# BMP180_breakout_v02.net
KiCad netlist of a schematic drawn in EAGLE
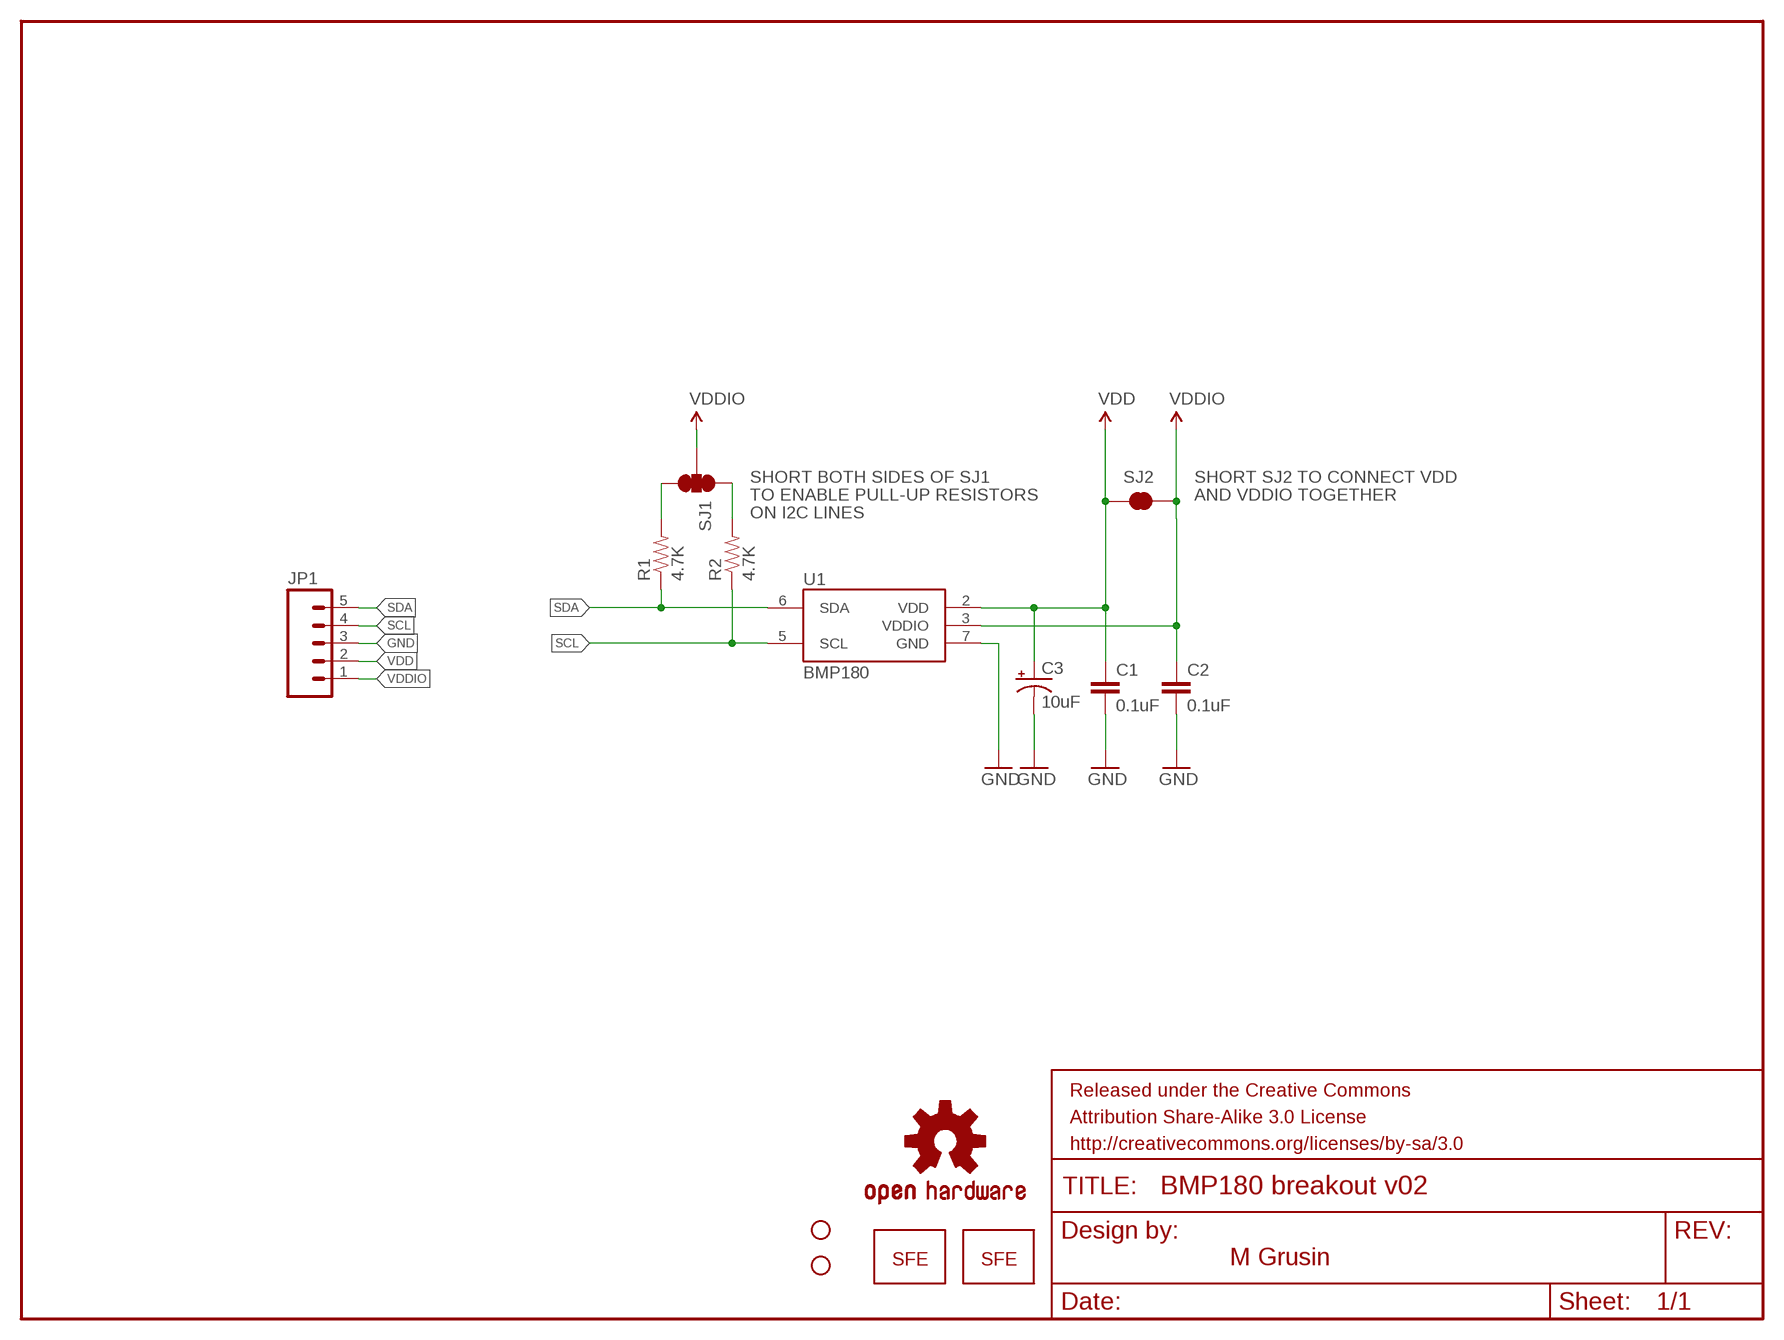
[diagram p0: schematic, sheet 1]

(export (version "E")
  (design (tool "Eeschema 10.0.6"))
  (components
    (comp (ref "C1")
      (value "0.1uF")
      (footprint "eagle-import:0603-CAP")
      (libsource (lib "eagle-import") (part "CAP0603-CAP"))
    )
    (comp (ref "C2")
      (value "0.1uF")
      (footprint "eagle-import:0603-CAP")
      (libsource (lib "eagle-import") (part "CAP0603-CAP"))
    )
    (comp (ref "C3")
      (value "10uF")
      (footprint "eagle-import:EIA3216")
      (libsource (lib "eagle-import") (part "10UF-16V-10%(TANT)"))
    )
    (comp (ref "FRAME1")
      (value "FRAME-LETTER")
      (footprint "eagle-import:CREATIVE_COMMONS")
      (libsource (lib "eagle-import") (part "FRAME-LETTER"))
    )
    (comp (ref "JP1")
      (value "M05_ROUNDONLY_NOSILK")
      (footprint "eagle-import:1X05_ROUNDONLY_NOSILK")
      (libsource (lib "eagle-import") (part "M05_ROUNDONLY_NOSILK"))
    )
    (comp (ref "LOGO1")
      (value "LOGO-SFENW2")
      (footprint "eagle-import:SFE-NEW-WEB")
      (libsource (lib "eagle-import") (part "LOGO-SFENW2"))
    )
    (comp (ref "LOGO2")
      (value "OSHW-LOGOS")
      (footprint "eagle-import:OSHW-LOGO-S")
      (libsource (lib "eagle-import") (part "OSHW-LOGOS"))
    )
    (comp (ref "LOGO3")
      (value "LOGO-SFESK")
      (footprint "eagle-import:SFE-LOGO-FLAME")
      (libsource (lib "eagle-import") (part "LOGO-SFESK"))
    )
    (comp (ref "R1")
      (value "4.7K")
      (footprint "eagle-import:0603-RES")
      (libsource (lib "eagle-import") (part "RESISTOR0603-RES"))
    )
    (comp (ref "R2")
      (value "4.7K")
      (footprint "eagle-import:0603-RES")
      (libsource (lib "eagle-import") (part "RESISTOR0603-RES"))
    )
    (comp (ref "SJ1")
      (value "SOLDERJUMPER_2WAYPASTE1&2&3")
      (footprint "eagle-import:SJ_3_PASTE1&2&3")
      (libsource (lib "eagle-import") (part "SOLDERJUMPER_2WAYPASTE1&2&3"))
    )
    (comp (ref "SJ2")
      (value "SOLDERJUMPERNC")
      (footprint "eagle-import:SJ_2S")
      (libsource (lib "eagle-import") (part "SOLDERJUMPERNC"))
    )
    (comp (ref "STANDOFF1")
      (value "STAND-OFF")
      (footprint "eagle-import:STAND-OFF")
      (libsource (lib "eagle-import") (part "STAND-OFF"))
    )
    (comp (ref "STANDOFF2")
      (value "STAND-OFF")
      (footprint "eagle-import:STAND-OFF")
      (libsource (lib "eagle-import") (part "STAND-OFF"))
    )
    (comp (ref "U1")
      (value "BMP180")
      (footprint "eagle-import:BMP180")
      (libsource (lib "eagle-import") (part "BMP180"))
    )
  )
  (nets
    (net (code "1") (name "GND") (class "Default")
      (node (ref "C1") (pin "2") (pinfunction "2_2") (pintype "passive"))
      (node (ref "C2") (pin "2") (pinfunction "2_2") (pintype "passive"))
      (node (ref "C3") (pin "C") (pinfunction "-_C") (pintype "passive"))
      (node (ref "JP1") (pin "3") (pinfunction "3_3") (pintype "passive"))
      (node (ref "U1") (pin "7") (pinfunction "GND_7") (pintype "power_in"))
    )
    (net (code "2") (name "Net-(R1-Pad2)") (class "Default")
      (node (ref "R1") (pin "2") (pinfunction "2_2") (pintype "passive"))
      (node (ref "SJ1") (pin "3") (pinfunction "3_3") (pintype "passive"))
    )
    (net (code "3") (name "Net-(R2-Pad2)") (class "Default")
      (node (ref "R2") (pin "2") (pinfunction "2_2") (pintype "passive"))
      (node (ref "SJ1") (pin "1") (pinfunction "1_1") (pintype "passive"))
    )
    (net (code "4") (name "SCL") (class "Default")
      (node (ref "JP1") (pin "4") (pinfunction "4_4") (pintype "passive"))
      (node (ref "R2") (pin "1") (pinfunction "1_1") (pintype "passive"))
      (node (ref "U1") (pin "5") (pinfunction "SCL_5") (pintype "input"))
    )
    (net (code "5") (name "SDA") (class "Default")
      (node (ref "JP1") (pin "5") (pinfunction "5_5") (pintype "passive"))
      (node (ref "R1") (pin "1") (pinfunction "1_1") (pintype "passive"))
      (node (ref "U1") (pin "6") (pinfunction "SDA_6") (pintype "bidirectional"))
    )
    (net (code "6") (name "VDD") (class "Default")
      (node (ref "C1") (pin "1") (pinfunction "1_1") (pintype "passive"))
      (node (ref "C3") (pin "A") (pinfunction "+_A") (pintype "passive"))
      (node (ref "JP1") (pin "2") (pinfunction "2_2") (pintype "passive"))
      (node (ref "SJ2") (pin "1") (pinfunction "1_1") (pintype "passive"))
      (node (ref "U1") (pin "2") (pinfunction "VDD_2") (pintype "power_in"))
    )
    (net (code "7") (name "VDDIO") (class "Default")
      (node (ref "C2") (pin "1") (pinfunction "1_1") (pintype "passive"))
      (node (ref "JP1") (pin "1") (pinfunction "1_1") (pintype "passive"))
      (node (ref "SJ1") (pin "2") (pinfunction "2_2") (pintype "passive"))
      (node (ref "SJ2") (pin "2") (pinfunction "2_2") (pintype "passive"))
      (node (ref "U1") (pin "3") (pinfunction "VDDIO_3") (pintype "power_in"))
    )
  )
)
